# Cartridge_Board_v0_1.net
KiCad netlist of a schematic drawn in EAGLE
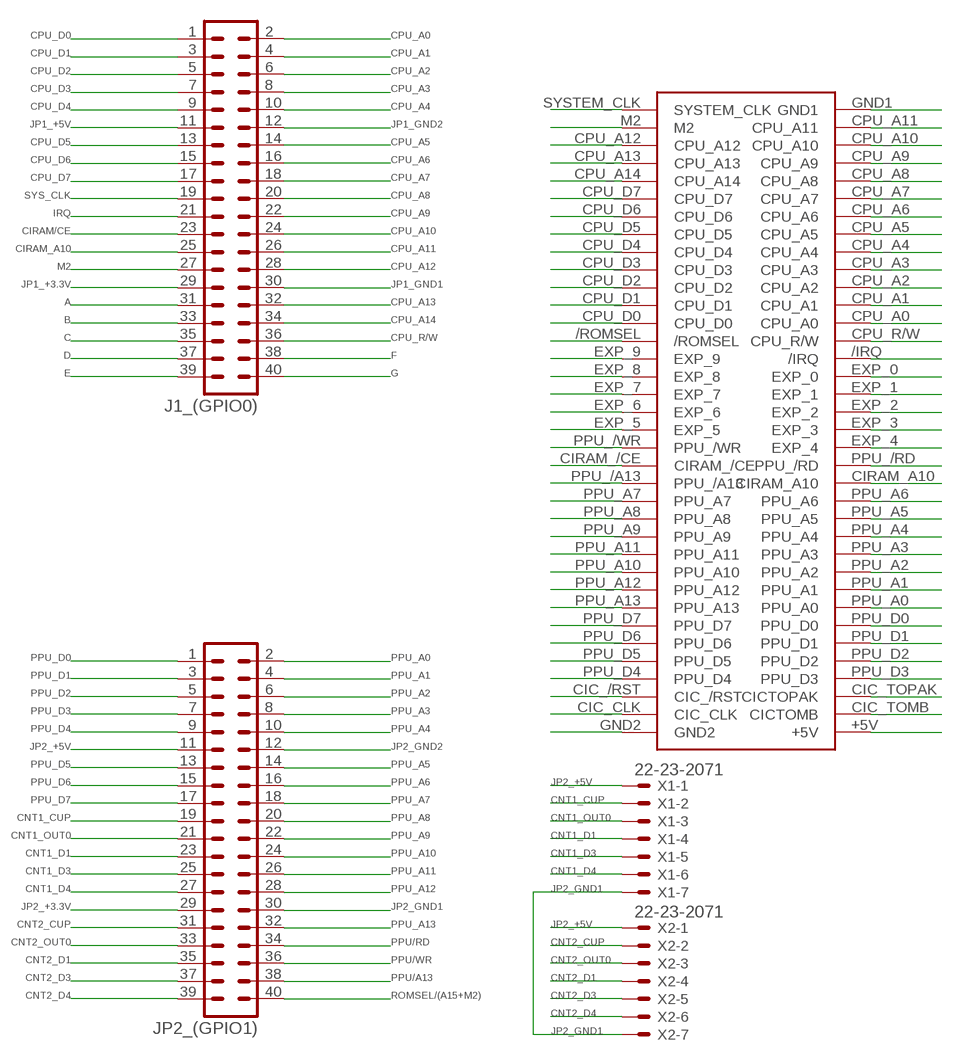
[diagram p0: schematic, sheet 1]

(export (version "E")
  (design (tool "Eeschema 10.0.6"))
  (components
    (comp (ref "J1_(GPIO0)")
      (value "40V")
      (footprint "eagle-import:40V")
      (libsource (lib "eagle-import") (part "40V"))
    )
    (comp (ref "JP2_(GPIO1)")
      (value "40V")
      (footprint "eagle-import:40V")
      (libsource (lib "eagle-import") (part "40V"))
    )
    (comp (ref "U$1")
      (value "CONNFEMALE72PIN0.1")
      (footprint "eagle-import:36X2")
      (libsource (lib "eagle-import") (part "CONNFEMALE72PIN0.1"))
    )
    (comp (ref "X1")
      (value "22-23-2071")
      (footprint "eagle-import:22-23-2071")
      (fields (field (name "MF") "MOLEX"))
      (libsource (lib "eagle-import") (part "22-23-2071"))
    )
    (comp (ref "X2")
      (value "22-23-2071")
      (footprint "eagle-import:22-23-2071")
      (fields (field (name "MF") "MOLEX"))
      (libsource (lib "eagle-import") (part "22-23-2071"))
    )
  )
  (nets
    (net (code "1") (name "/A") (class "Default")
      (node (ref "J1_(GPIO0)") (pin "31") (pinfunction "31_31") (pintype "passive"))
    )
    (net (code "2") (name "/B") (class "Default")
      (node (ref "J1_(GPIO0)") (pin "33") (pinfunction "33_33") (pintype "passive"))
    )
    (net (code "3") (name "/C") (class "Default")
      (node (ref "J1_(GPIO0)") (pin "35") (pinfunction "35_35") (pintype "passive"))
    )
    (net (code "4") (name "/CIRAM_A10") (class "Default")
      (node (ref "J1_(GPIO0)") (pin "25") (pinfunction "25_25") (pintype "passive"))
      (node (ref "U$1") (pin "CIRAM_A10") (pinfunction "CIRAM_A10_CIRAM_A10") (pintype "bidirectional"))
    )
    (net (code "5") (name "/CIRAM{slash}CE") (class "Default")
      (node (ref "J1_(GPIO0)") (pin "23") (pinfunction "23_23") (pintype "passive"))
      (node (ref "U$1") (pin "CIRAM_/CE") (pinfunction "CIRAM_/CE_CIRAM_/CE") (pintype "bidirectional"))
    )
    (net (code "6") (name "/CNT1_CUP") (class "Default")
      (node (ref "JP2_(GPIO1)") (pin "19") (pinfunction "19_19") (pintype "passive"))
      (node (ref "X1") (pin "2") (pinfunction "S_2") (pintype "passive"))
    )
    (net (code "7") (name "/CNT1_D1") (class "Default")
      (node (ref "JP2_(GPIO1)") (pin "23") (pinfunction "23_23") (pintype "passive"))
      (node (ref "X1") (pin "4") (pinfunction "S_4") (pintype "passive"))
    )
    (net (code "8") (name "/CNT1_D3") (class "Default")
      (node (ref "JP2_(GPIO1)") (pin "25") (pinfunction "25_25") (pintype "passive"))
      (node (ref "X1") (pin "5") (pinfunction "S_5") (pintype "passive"))
    )
    (net (code "9") (name "/CNT1_D4") (class "Default")
      (node (ref "JP2_(GPIO1)") (pin "27") (pinfunction "27_27") (pintype "passive"))
      (node (ref "X1") (pin "6") (pinfunction "S_6") (pintype "passive"))
    )
    (net (code "10") (name "/CNT1_OUT0") (class "Default")
      (node (ref "JP2_(GPIO1)") (pin "21") (pinfunction "21_21") (pintype "passive"))
      (node (ref "X1") (pin "3") (pinfunction "S_3") (pintype "passive"))
    )
    (net (code "11") (name "/CNT2_CUP") (class "Default")
      (node (ref "JP2_(GPIO1)") (pin "31") (pinfunction "31_31") (pintype "passive"))
      (node (ref "X2") (pin "2") (pinfunction "S_2") (pintype "passive"))
    )
    (net (code "12") (name "/CNT2_D1") (class "Default")
      (node (ref "JP2_(GPIO1)") (pin "35") (pinfunction "35_35") (pintype "passive"))
      (node (ref "X2") (pin "4") (pinfunction "S_4") (pintype "passive"))
    )
    (net (code "13") (name "/CNT2_D3") (class "Default")
      (node (ref "JP2_(GPIO1)") (pin "37") (pinfunction "37_37") (pintype "passive"))
      (node (ref "X2") (pin "5") (pinfunction "S_5") (pintype "passive"))
    )
    (net (code "14") (name "/CNT2_D4") (class "Default")
      (node (ref "JP2_(GPIO1)") (pin "39") (pinfunction "39_39") (pintype "passive"))
      (node (ref "X2") (pin "6") (pinfunction "S_6") (pintype "passive"))
    )
    (net (code "15") (name "/CNT2_OUT0") (class "Default")
      (node (ref "JP2_(GPIO1)") (pin "33") (pinfunction "33_33") (pintype "passive"))
      (node (ref "X2") (pin "3") (pinfunction "S_3") (pintype "passive"))
    )
    (net (code "16") (name "/CPU_A0") (class "Default")
      (node (ref "J1_(GPIO0)") (pin "2") (pinfunction "2_2") (pintype "passive"))
      (node (ref "U$1") (pin "CPU_A0") (pinfunction "CPU_A0_CPU_A0") (pintype "bidirectional"))
    )
    (net (code "17") (name "/CPU_A1") (class "Default")
      (node (ref "J1_(GPIO0)") (pin "4") (pinfunction "4_4") (pintype "passive"))
      (node (ref "U$1") (pin "CPU_A1") (pinfunction "CPU_A1_CPU_A1") (pintype "bidirectional"))
    )
    (net (code "18") (name "/CPU_A2") (class "Default")
      (node (ref "J1_(GPIO0)") (pin "6") (pinfunction "6_6") (pintype "passive"))
      (node (ref "U$1") (pin "CPU_A2") (pinfunction "CPU_A2_CPU_A2") (pintype "bidirectional"))
    )
    (net (code "19") (name "/CPU_A3") (class "Default")
      (node (ref "J1_(GPIO0)") (pin "8") (pinfunction "8_8") (pintype "passive"))
      (node (ref "U$1") (pin "CPU_A3") (pinfunction "CPU_A3_CPU_A3") (pintype "bidirectional"))
    )
    (net (code "20") (name "/CPU_A4") (class "Default")
      (node (ref "J1_(GPIO0)") (pin "10") (pinfunction "10_10") (pintype "passive"))
      (node (ref "U$1") (pin "CPU_A4") (pinfunction "CPU_A4_CPU_A4") (pintype "bidirectional"))
    )
    (net (code "21") (name "/CPU_A5") (class "Default")
      (node (ref "J1_(GPIO0)") (pin "14") (pinfunction "14_14") (pintype "passive"))
      (node (ref "U$1") (pin "CPU_A5") (pinfunction "CPU_A5_CPU_A5") (pintype "bidirectional"))
    )
    (net (code "22") (name "/CPU_A6") (class "Default")
      (node (ref "J1_(GPIO0)") (pin "16") (pinfunction "16_16") (pintype "passive"))
      (node (ref "U$1") (pin "CPU_A6") (pinfunction "CPU_A6_CPU_A6") (pintype "bidirectional"))
    )
    (net (code "23") (name "/CPU_A7") (class "Default")
      (node (ref "J1_(GPIO0)") (pin "18") (pinfunction "18_18") (pintype "passive"))
      (node (ref "U$1") (pin "CPU_A7") (pinfunction "CPU_A7_CPU_A7") (pintype "bidirectional"))
    )
    (net (code "24") (name "/CPU_A8") (class "Default")
      (node (ref "J1_(GPIO0)") (pin "20") (pinfunction "20_20") (pintype "passive"))
      (node (ref "U$1") (pin "CPU_A8") (pinfunction "CPU_A8_CPU_A8") (pintype "bidirectional"))
    )
    (net (code "25") (name "/CPU_A9") (class "Default")
      (node (ref "J1_(GPIO0)") (pin "22") (pinfunction "22_22") (pintype "passive"))
      (node (ref "U$1") (pin "CPU_A9") (pinfunction "CPU_A9_CPU_A9") (pintype "bidirectional"))
    )
    (net (code "26") (name "/CPU_A10") (class "Default")
      (node (ref "J1_(GPIO0)") (pin "24") (pinfunction "24_24") (pintype "passive"))
      (node (ref "U$1") (pin "CPU_A10") (pinfunction "CPU_A10_CPU_A10") (pintype "bidirectional"))
    )
    (net (code "27") (name "/CPU_A11") (class "Default")
      (node (ref "J1_(GPIO0)") (pin "26") (pinfunction "26_26") (pintype "passive"))
      (node (ref "U$1") (pin "CPU_A11") (pinfunction "CPU_A11_CPU_A11") (pintype "bidirectional"))
    )
    (net (code "28") (name "/CPU_A12") (class "Default")
      (node (ref "J1_(GPIO0)") (pin "28") (pinfunction "28_28") (pintype "passive"))
      (node (ref "U$1") (pin "CPU_A12") (pinfunction "CPU_A12_CPU_A12") (pintype "bidirectional"))
    )
    (net (code "29") (name "/CPU_A13") (class "Default")
      (node (ref "J1_(GPIO0)") (pin "32") (pinfunction "32_32") (pintype "passive"))
      (node (ref "U$1") (pin "CPU_A13") (pinfunction "CPU_A13_CPU_A13") (pintype "bidirectional"))
    )
    (net (code "30") (name "/CPU_A14") (class "Default")
      (node (ref "J1_(GPIO0)") (pin "34") (pinfunction "34_34") (pintype "passive"))
      (node (ref "U$1") (pin "CPU_A14") (pinfunction "CPU_A14_CPU_A14") (pintype "bidirectional"))
    )
    (net (code "31") (name "/CPU_D0") (class "Default")
      (node (ref "J1_(GPIO0)") (pin "1") (pinfunction "1_1") (pintype "passive"))
      (node (ref "U$1") (pin "CPU_D0") (pinfunction "CPU_D0_CPU_D0") (pintype "bidirectional"))
    )
    (net (code "32") (name "/CPU_D1") (class "Default")
      (node (ref "J1_(GPIO0)") (pin "3") (pinfunction "3_3") (pintype "passive"))
      (node (ref "U$1") (pin "CPU_D1") (pinfunction "CPU_D1_CPU_D1") (pintype "bidirectional"))
    )
    (net (code "33") (name "/CPU_D2") (class "Default")
      (node (ref "J1_(GPIO0)") (pin "5") (pinfunction "5_5") (pintype "passive"))
      (node (ref "U$1") (pin "CPU_D2") (pinfunction "CPU_D2_CPU_D2") (pintype "bidirectional"))
    )
    (net (code "34") (name "/CPU_D3") (class "Default")
      (node (ref "J1_(GPIO0)") (pin "7") (pinfunction "7_7") (pintype "passive"))
      (node (ref "U$1") (pin "CPU_D3") (pinfunction "CPU_D3_CPU_D3") (pintype "bidirectional"))
    )
    (net (code "35") (name "/CPU_D4") (class "Default")
      (node (ref "J1_(GPIO0)") (pin "9") (pinfunction "9_9") (pintype "passive"))
      (node (ref "U$1") (pin "CPU_D4") (pinfunction "CPU_D4_CPU_D4") (pintype "bidirectional"))
    )
    (net (code "36") (name "/CPU_D5") (class "Default")
      (node (ref "J1_(GPIO0)") (pin "13") (pinfunction "13_13") (pintype "passive"))
      (node (ref "U$1") (pin "CPU_D5") (pinfunction "CPU_D5_CPU_D5") (pintype "bidirectional"))
    )
    (net (code "37") (name "/CPU_D6") (class "Default")
      (node (ref "J1_(GPIO0)") (pin "15") (pinfunction "15_15") (pintype "passive"))
      (node (ref "U$1") (pin "CPU_D6") (pinfunction "CPU_D6_CPU_D6") (pintype "bidirectional"))
    )
    (net (code "38") (name "/CPU_D7") (class "Default")
      (node (ref "J1_(GPIO0)") (pin "17") (pinfunction "17_17") (pintype "passive"))
      (node (ref "U$1") (pin "CPU_D7") (pinfunction "CPU_D7_CPU_D7") (pintype "bidirectional"))
    )
    (net (code "39") (name "/CPU_R{slash}W") (class "Default")
      (node (ref "J1_(GPIO0)") (pin "36") (pinfunction "36_36") (pintype "passive"))
      (node (ref "U$1") (pin "CPU_R/W") (pinfunction "CPU_R/W_CPU_R/W") (pintype "bidirectional"))
    )
    (net (code "40") (name "/D") (class "Default")
      (node (ref "J1_(GPIO0)") (pin "37") (pinfunction "37_37") (pintype "passive"))
    )
    (net (code "41") (name "/E") (class "Default")
      (node (ref "J1_(GPIO0)") (pin "39") (pinfunction "39_39") (pintype "passive"))
    )
    (net (code "42") (name "/F") (class "Default")
      (node (ref "J1_(GPIO0)") (pin "38") (pinfunction "38_38") (pintype "passive"))
    )
    (net (code "43") (name "/G") (class "Default")
      (node (ref "J1_(GPIO0)") (pin "40") (pinfunction "40_40") (pintype "passive"))
    )
    (net (code "44") (name "/IRQ") (class "Default")
      (node (ref "J1_(GPIO0)") (pin "21") (pinfunction "21_21") (pintype "passive"))
      (node (ref "U$1") (pin "/IRQ") (pinfunction "/IRQ_/IRQ") (pintype "bidirectional"))
    )
    (net (code "45") (name "/JP1_+3.3V") (class "Default")
      (node (ref "J1_(GPIO0)") (pin "29") (pinfunction "29_29") (pintype "passive"))
    )
    (net (code "46") (name "/JP1_+5V") (class "Default")
      (node (ref "J1_(GPIO0)") (pin "11") (pinfunction "11_11") (pintype "passive"))
    )
    (net (code "47") (name "/JP1_GND1") (class "Default")
      (node (ref "J1_(GPIO0)") (pin "30") (pinfunction "30_30") (pintype "passive"))
      (node (ref "U$1") (pin "GND1") (pinfunction "GND1_GND1") (pintype "bidirectional"))
      (node (ref "U$1") (pin "GND2") (pinfunction "GND2_GND2") (pintype "bidirectional"))
    )
    (net (code "48") (name "/JP1_GND2") (class "Default")
      (node (ref "J1_(GPIO0)") (pin "12") (pinfunction "12_12") (pintype "passive"))
    )
    (net (code "49") (name "/JP2_+3.3V") (class "Default")
      (node (ref "JP2_(GPIO1)") (pin "29") (pinfunction "29_29") (pintype "passive"))
    )
    (net (code "50") (name "/JP2_+5V") (class "Default")
      (node (ref "JP2_(GPIO1)") (pin "11") (pinfunction "11_11") (pintype "passive"))
      (node (ref "U$1") (pin "+5V") (pinfunction "+5V_+5V") (pintype "bidirectional"))
      (node (ref "X1") (pin "1") (pinfunction "S_1") (pintype "passive"))
      (node (ref "X2") (pin "1") (pinfunction "S_1") (pintype "passive"))
    )
    (net (code "51") (name "/JP2_GND1") (class "Default")
      (node (ref "JP2_(GPIO1)") (pin "30") (pinfunction "30_30") (pintype "passive"))
      (node (ref "X1") (pin "7") (pinfunction "S_7") (pintype "passive"))
      (node (ref "X2") (pin "7") (pinfunction "S_7") (pintype "passive"))
    )
    (net (code "52") (name "/JP2_GND2") (class "Default")
      (node (ref "JP2_(GPIO1)") (pin "12") (pinfunction "12_12") (pintype "passive"))
    )
    (net (code "53") (name "/M2") (class "Default")
      (node (ref "J1_(GPIO0)") (pin "27") (pinfunction "27_27") (pintype "passive"))
      (node (ref "U$1") (pin "M2") (pinfunction "M2_M2") (pintype "bidirectional"))
    )
    (net (code "54") (name "/PPU_A0") (class "Default")
      (node (ref "JP2_(GPIO1)") (pin "2") (pinfunction "2_2") (pintype "passive"))
      (node (ref "U$1") (pin "PPU_A0") (pinfunction "PPU_A0_PPU_A0") (pintype "bidirectional"))
    )
    (net (code "55") (name "/PPU_A1") (class "Default")
      (node (ref "JP2_(GPIO1)") (pin "4") (pinfunction "4_4") (pintype "passive"))
      (node (ref "U$1") (pin "PPU_A1") (pinfunction "PPU_A1_PPU_A1") (pintype "bidirectional"))
    )
    (net (code "56") (name "/PPU_A2") (class "Default")
      (node (ref "JP2_(GPIO1)") (pin "6") (pinfunction "6_6") (pintype "passive"))
      (node (ref "U$1") (pin "PPU_A2") (pinfunction "PPU_A2_PPU_A2") (pintype "bidirectional"))
    )
    (net (code "57") (name "/PPU_A3") (class "Default")
      (node (ref "JP2_(GPIO1)") (pin "8") (pinfunction "8_8") (pintype "passive"))
      (node (ref "U$1") (pin "PPU_A3") (pinfunction "PPU_A3_PPU_A3") (pintype "bidirectional"))
    )
    (net (code "58") (name "/PPU_A4") (class "Default")
      (node (ref "JP2_(GPIO1)") (pin "10") (pinfunction "10_10") (pintype "passive"))
      (node (ref "U$1") (pin "PPU_A4") (pinfunction "PPU_A4_PPU_A4") (pintype "bidirectional"))
    )
    (net (code "59") (name "/PPU_A5") (class "Default")
      (node (ref "JP2_(GPIO1)") (pin "14") (pinfunction "14_14") (pintype "passive"))
      (node (ref "U$1") (pin "PPU_A5") (pinfunction "PPU_A5_PPU_A5") (pintype "bidirectional"))
    )
    (net (code "60") (name "/PPU_A6") (class "Default")
      (node (ref "JP2_(GPIO1)") (pin "16") (pinfunction "16_16") (pintype "passive"))
      (node (ref "U$1") (pin "PPU_A6") (pinfunction "PPU_A6_PPU_A6") (pintype "bidirectional"))
    )
    (net (code "61") (name "/PPU_A7") (class "Default")
      (node (ref "JP2_(GPIO1)") (pin "18") (pinfunction "18_18") (pintype "passive"))
      (node (ref "U$1") (pin "PPU_A7") (pinfunction "PPU_A7_PPU_A7") (pintype "bidirectional"))
    )
    (net (code "62") (name "/PPU_A8") (class "Default")
      (node (ref "JP2_(GPIO1)") (pin "20") (pinfunction "20_20") (pintype "passive"))
      (node (ref "U$1") (pin "PPU_A8") (pinfunction "PPU_A8_PPU_A8") (pintype "bidirectional"))
    )
    (net (code "63") (name "/PPU_A9") (class "Default")
      (node (ref "JP2_(GPIO1)") (pin "22") (pinfunction "22_22") (pintype "passive"))
      (node (ref "U$1") (pin "PPU_A9") (pinfunction "PPU_A9_PPU_A9") (pintype "bidirectional"))
    )
    (net (code "64") (name "/PPU_A10") (class "Default")
      (node (ref "JP2_(GPIO1)") (pin "24") (pinfunction "24_24") (pintype "passive"))
      (node (ref "U$1") (pin "PPU_A10") (pinfunction "PPU_A10_PPU_A10") (pintype "bidirectional"))
    )
    (net (code "65") (name "/PPU_A11") (class "Default")
      (node (ref "JP2_(GPIO1)") (pin "26") (pinfunction "26_26") (pintype "passive"))
      (node (ref "U$1") (pin "PPU_A11") (pinfunction "PPU_A11_PPU_A11") (pintype "bidirectional"))
    )
    (net (code "66") (name "/PPU_A12") (class "Default")
      (node (ref "JP2_(GPIO1)") (pin "28") (pinfunction "28_28") (pintype "passive"))
      (node (ref "U$1") (pin "PPU_A12") (pinfunction "PPU_A12_PPU_A12") (pintype "bidirectional"))
    )
    (net (code "67") (name "/PPU_A13") (class "Default")
      (node (ref "JP2_(GPIO1)") (pin "32") (pinfunction "32_32") (pintype "passive"))
      (node (ref "U$1") (pin "PPU_A13") (pinfunction "PPU_A13_PPU_A13") (pintype "bidirectional"))
    )
    (net (code "68") (name "/PPU_D0") (class "Default")
      (node (ref "JP2_(GPIO1)") (pin "1") (pinfunction "1_1") (pintype "passive"))
      (node (ref "U$1") (pin "PPU_D0") (pinfunction "PPU_D0_PPU_D0") (pintype "bidirectional"))
    )
    (net (code "69") (name "/PPU_D1") (class "Default")
      (node (ref "JP2_(GPIO1)") (pin "3") (pinfunction "3_3") (pintype "passive"))
      (node (ref "U$1") (pin "PPU_D1") (pinfunction "PPU_D1_PPU_D1") (pintype "bidirectional"))
    )
    (net (code "70") (name "/PPU_D2") (class "Default")
      (node (ref "JP2_(GPIO1)") (pin "5") (pinfunction "5_5") (pintype "passive"))
      (node (ref "U$1") (pin "PPU_D2") (pinfunction "PPU_D2_PPU_D2") (pintype "bidirectional"))
    )
    (net (code "71") (name "/PPU_D3") (class "Default")
      (node (ref "JP2_(GPIO1)") (pin "7") (pinfunction "7_7") (pintype "passive"))
      (node (ref "U$1") (pin "PPU_D3") (pinfunction "PPU_D3_PPU_D3") (pintype "bidirectional"))
    )
    (net (code "72") (name "/PPU_D4") (class "Default")
      (node (ref "JP2_(GPIO1)") (pin "9") (pinfunction "9_9") (pintype "passive"))
      (node (ref "U$1") (pin "PPU_D4") (pinfunction "PPU_D4_PPU_D4") (pintype "bidirectional"))
    )
    (net (code "73") (name "/PPU_D5") (class "Default")
      (node (ref "JP2_(GPIO1)") (pin "13") (pinfunction "13_13") (pintype "passive"))
      (node (ref "U$1") (pin "PPU_D5") (pinfunction "PPU_D5_PPU_D5") (pintype "bidirectional"))
    )
    (net (code "74") (name "/PPU_D6") (class "Default")
      (node (ref "JP2_(GPIO1)") (pin "15") (pinfunction "15_15") (pintype "passive"))
      (node (ref "U$1") (pin "PPU_D6") (pinfunction "PPU_D6_PPU_D6") (pintype "bidirectional"))
    )
    (net (code "75") (name "/PPU_D7") (class "Default")
      (node (ref "JP2_(GPIO1)") (pin "17") (pinfunction "17_17") (pintype "passive"))
      (node (ref "U$1") (pin "PPU_D7") (pinfunction "PPU_D7_PPU_D7") (pintype "bidirectional"))
    )
    (net (code "76") (name "/PPU{slash}A13") (class "Default")
      (node (ref "JP2_(GPIO1)") (pin "38") (pinfunction "38_38") (pintype "passive"))
      (node (ref "U$1") (pin "PPU_/A13") (pinfunction "PPU_/A13_PPU_/A13") (pintype "bidirectional"))
    )
    (net (code "77") (name "/PPU{slash}RD") (class "Default")
      (node (ref "JP2_(GPIO1)") (pin "34") (pinfunction "34_34") (pintype "passive"))
      (node (ref "U$1") (pin "PPU_/RD") (pinfunction "PPU_/RD_PPU_/RD") (pintype "bidirectional"))
    )
    (net (code "78") (name "/PPU{slash}WR") (class "Default")
      (node (ref "JP2_(GPIO1)") (pin "36") (pinfunction "36_36") (pintype "passive"))
      (node (ref "U$1") (pin "PPU_/WR") (pinfunction "PPU_/WR_PPU_/WR") (pintype "bidirectional"))
    )
    (net (code "79") (name "/ROMSEL{slash}(A15+M2)") (class "Default")
      (node (ref "JP2_(GPIO1)") (pin "40") (pinfunction "40_40") (pintype "passive"))
      (node (ref "U$1") (pin "/ROMSEL") (pinfunction "/ROMSEL_/ROMSEL") (pintype "bidirectional"))
    )
    (net (code "80") (name "/SYS_CLK") (class "Default")
      (node (ref "J1_(GPIO0)") (pin "19") (pinfunction "19_19") (pintype "passive"))
      (node (ref "U$1") (pin "SYSTEM_CLK") (pinfunction "SYSTEM_CLK_SYSTEM_CLK") (pintype "bidirectional"))
    )
    (net (code "81") (name "unconnected-(U$1-CICTOMB-PadCIC_TOMB)") (class "Default")
      (node (ref "U$1") (pin "CIC_TOMB") (pinfunction "CICTOMB_CIC_TOMB") (pintype "bidirectional"))
    )
    (net (code "82") (name "unconnected-(U$1-CICTOPAK-PadCIC_TOPAK)") (class "Default")
      (node (ref "U$1") (pin "CIC_TOPAK") (pinfunction "CICTOPAK_CIC_TOPAK") (pintype "bidirectional"))
    )
    (net (code "83") (name "unconnected-(U$1-PadCIC_CLK)") (class "Default")
      (node (ref "U$1") (pin "CIC_CLK") (pinfunction "CIC_CLK_CIC_CLK") (pintype "bidirectional"))
    )
    (net (code "84") (name "unconnected-(U$1-PadCIC_{slash}RST)") (class "Default")
      (node (ref "U$1") (pin "CIC_/RST") (pinfunction "CIC_/RST_CIC_/RST") (pintype "bidirectional"))
    )
    (net (code "85") (name "unconnected-(U$1-PadEXP_0)") (class "Default")
      (node (ref "U$1") (pin "EXP_0") (pinfunction "EXP_0_EXP_0") (pintype "bidirectional"))
    )
    (net (code "86") (name "unconnected-(U$1-PadEXP_1)") (class "Default")
      (node (ref "U$1") (pin "EXP_1") (pinfunction "EXP_1_EXP_1") (pintype "bidirectional"))
    )
    (net (code "87") (name "unconnected-(U$1-PadEXP_2)") (class "Default")
      (node (ref "U$1") (pin "EXP_2") (pinfunction "EXP_2_EXP_2") (pintype "bidirectional"))
    )
    (net (code "88") (name "unconnected-(U$1-PadEXP_3)") (class "Default")
      (node (ref "U$1") (pin "EXP_3") (pinfunction "EXP_3_EXP_3") (pintype "bidirectional"))
    )
    (net (code "89") (name "unconnected-(U$1-PadEXP_4)") (class "Default")
      (node (ref "U$1") (pin "EXP_4") (pinfunction "EXP_4_EXP_4") (pintype "bidirectional"))
    )
    (net (code "90") (name "unconnected-(U$1-PadEXP_5)") (class "Default")
      (node (ref "U$1") (pin "EXP_5") (pinfunction "EXP_5_EXP_5") (pintype "bidirectional"))
    )
    (net (code "91") (name "unconnected-(U$1-PadEXP_6)") (class "Default")
      (node (ref "U$1") (pin "EXP_6") (pinfunction "EXP_6_EXP_6") (pintype "bidirectional"))
    )
    (net (code "92") (name "unconnected-(U$1-PadEXP_7)") (class "Default")
      (node (ref "U$1") (pin "EXP_7") (pinfunction "EXP_7_EXP_7") (pintype "bidirectional"))
    )
    (net (code "93") (name "unconnected-(U$1-PadEXP_8)") (class "Default")
      (node (ref "U$1") (pin "EXP_8") (pinfunction "EXP_8_EXP_8") (pintype "bidirectional"))
    )
    (net (code "94") (name "unconnected-(U$1-PadEXP_9)") (class "Default")
      (node (ref "U$1") (pin "EXP_9") (pinfunction "EXP_9_EXP_9") (pintype "bidirectional"))
    )
  )
)
